# Troopduino.net
KiCad netlist of a schematic drawn in EAGLE
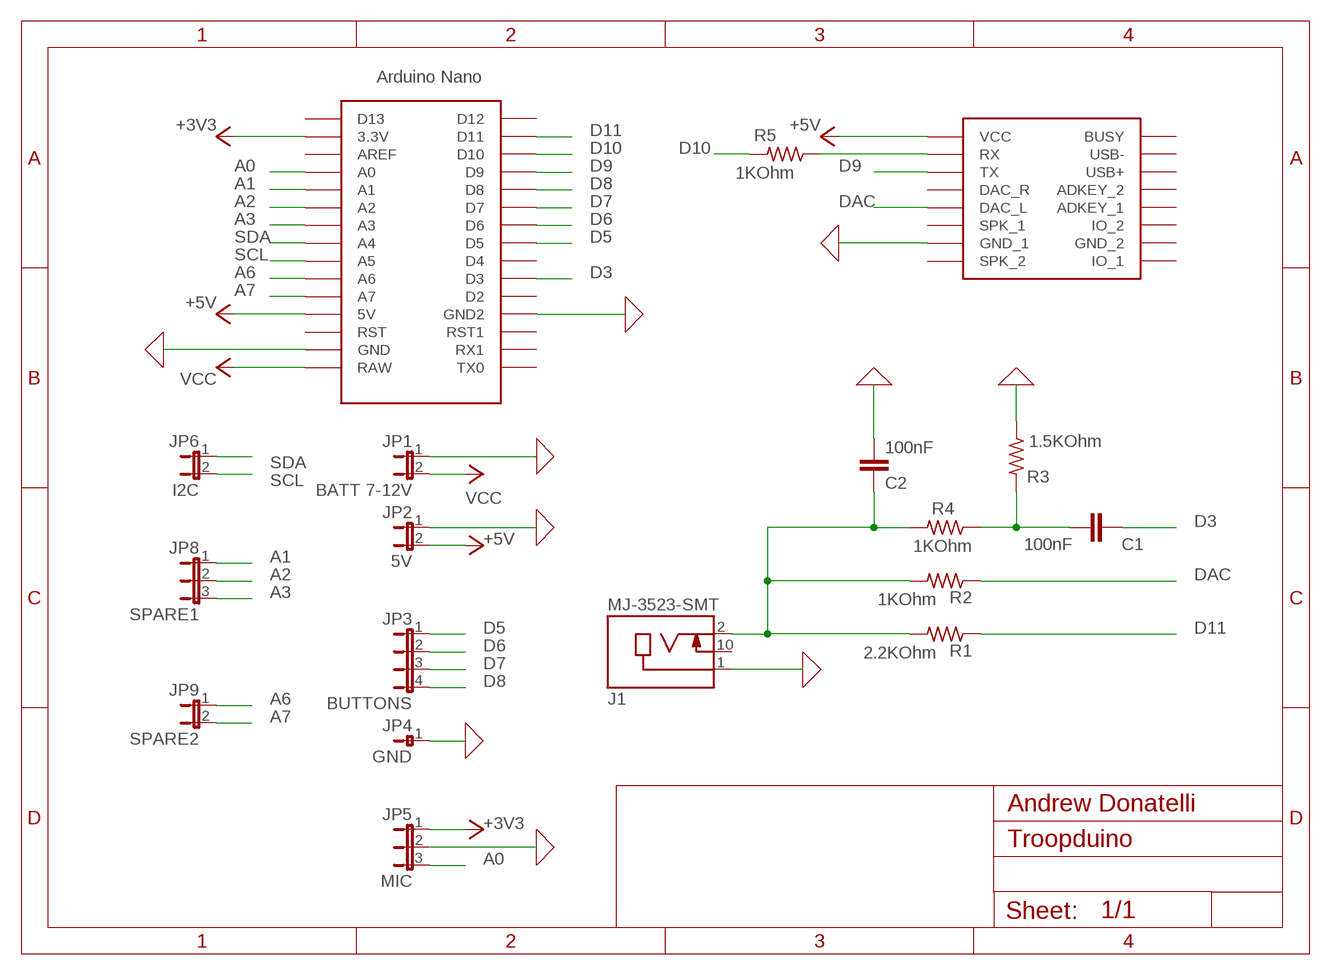
[diagram p0: schematic, sheet 1]

(export (version "E")
  (design (tool "Eeschema 10.0.6"))
  (components
    (comp (ref "C1")
      (value "100nF")
      (footprint "eagle-import:C0805")
      (libsource (lib "eagle-import") (part "C-EUC0805"))
    )
    (comp (ref "C2")
      (value "100nF")
      (footprint "eagle-import:C0805")
      (libsource (lib "eagle-import") (part "C-EUC0805"))
    )
    (comp (ref "J1")
      (value "MJ-3523-SMT")
      (footprint "eagle-import:CUI_MJ-3523-SMT")
      (fields (field (name "MANUFACTURER") "CUI INC"))
      (libsource (lib "eagle-import") (part "MJ-3523-SMT"))
    )
    (comp (ref "JP1")
      (value "BATT 7-12V")
      (footprint "eagle-import:JP1")
      (libsource (lib "eagle-import") (part "JP1E"))
    )
    (comp (ref "JP2")
      (value "5V")
      (footprint "eagle-import:JP1")
      (libsource (lib "eagle-import") (part "JP1E"))
    )
    (comp (ref "JP3")
      (value "BUTTONS")
      (footprint "eagle-import:JP4")
      (libsource (lib "eagle-import") (part "JP4E"))
    )
    (comp (ref "JP4")
      (value "GND")
      (footprint "eagle-import:JP0")
      (libsource (lib "eagle-import") (part "JP0EJP0"))
    )
    (comp (ref "JP5")
      (value "MIC")
      (footprint "eagle-import:JP2")
      (libsource (lib "eagle-import") (part "JP2E"))
    )
    (comp (ref "JP6")
      (value "I2C")
      (footprint "eagle-import:JP1")
      (libsource (lib "eagle-import") (part "JP1E"))
    )
    (comp (ref "JP8")
      (value "SPARE1")
      (footprint "eagle-import:JP2")
      (libsource (lib "eagle-import") (part "JP2E"))
    )
    (comp (ref "JP9")
      (value "SPARE2")
      (footprint "eagle-import:JP1")
      (libsource (lib "eagle-import") (part "JP1E"))
    )
    (comp (ref "R1")
      (value "2.2KOhm")
      (footprint "eagle-import:M0805")
      (libsource (lib "eagle-import") (part "R-US_M0805"))
    )
    (comp (ref "R2")
      (value "1KOhm")
      (footprint "eagle-import:M0805")
      (libsource (lib "eagle-import") (part "R-US_M0805"))
    )
    (comp (ref "R3")
      (value "1.5KOhm")
      (footprint "eagle-import:M0805")
      (libsource (lib "eagle-import") (part "R-US_M0805"))
    )
    (comp (ref "R4")
      (value "1KOhm")
      (footprint "eagle-import:M0805")
      (libsource (lib "eagle-import") (part "R-US_M0805"))
    )
    (comp (ref "R5")
      (value "1KOhm")
      (footprint "eagle-import:M0805")
      (libsource (lib "eagle-import") (part "R-US_M0805"))
    )
    (comp (ref "U$1")
      (value "DFPLAYER")
      (footprint "eagle-import:DFPLAYER")
      (libsource (lib "eagle-import") (part "DFPLAYER"))
    )
    (comp (ref "U$2")
      (value "NANO")
      (footprint "eagle-import:NANO")
      (libsource (lib "eagle-import") (part "NANO"))
    )
  )
  (nets
    (net (code "1") (name "+3V3") (class "Default")
      (node (ref "JP5") (pin "1") (pinfunction "1_1") (pintype "passive"))
      (node (ref "U$2") (pin "3.3V") (pinfunction "3.3V_3.3V") (pintype "bidirectional"))
    )
    (net (code "2") (name "+5V") (class "Default")
      (node (ref "JP2") (pin "2") (pinfunction "2_2") (pintype "passive"))
      (node (ref "U$1") (pin "VCC") (pinfunction "VCC_VCC") (pintype "bidirectional"))
      (node (ref "U$2") (pin "5V") (pinfunction "5V_5V") (pintype "bidirectional"))
    )
    (net (code "3") (name "/A0") (class "Default")
      (node (ref "JP5") (pin "3") (pinfunction "3_3") (pintype "passive"))
      (node (ref "U$2") (pin "A0") (pinfunction "A0_A0") (pintype "bidirectional"))
    )
    (net (code "4") (name "/A1") (class "Default")
      (node (ref "JP8") (pin "1") (pinfunction "1_1") (pintype "passive"))
      (node (ref "U$2") (pin "A1") (pinfunction "A1_A1") (pintype "bidirectional"))
    )
    (net (code "5") (name "/A2") (class "Default")
      (node (ref "JP8") (pin "2") (pinfunction "2_2") (pintype "passive"))
      (node (ref "U$2") (pin "A2") (pinfunction "A2_A2") (pintype "bidirectional"))
    )
    (net (code "6") (name "/A3") (class "Default")
      (node (ref "JP8") (pin "3") (pinfunction "3_3") (pintype "passive"))
      (node (ref "U$2") (pin "A3") (pinfunction "A3_A3") (pintype "bidirectional"))
    )
    (net (code "7") (name "/A6") (class "Default")
      (node (ref "JP9") (pin "1") (pinfunction "1_1") (pintype "passive"))
      (node (ref "U$2") (pin "A6") (pinfunction "A6_A6") (pintype "bidirectional"))
    )
    (net (code "8") (name "/A7") (class "Default")
      (node (ref "JP9") (pin "2") (pinfunction "2_2") (pintype "passive"))
      (node (ref "U$2") (pin "A7") (pinfunction "A7_A7") (pintype "bidirectional"))
    )
    (net (code "9") (name "/D3") (class "Default")
      (node (ref "C1") (pin "1") (pinfunction "1_1") (pintype "passive"))
      (node (ref "U$2") (pin "D3") (pinfunction "D3_D3") (pintype "bidirectional"))
    )
    (net (code "10") (name "/D5") (class "Default")
      (node (ref "JP3") (pin "1") (pinfunction "1_1") (pintype "passive"))
      (node (ref "U$2") (pin "D5") (pinfunction "D5_D5") (pintype "bidirectional"))
    )
    (net (code "11") (name "/D6") (class "Default")
      (node (ref "JP3") (pin "2") (pinfunction "2_2") (pintype "passive"))
      (node (ref "U$2") (pin "D6") (pinfunction "D6_D6") (pintype "bidirectional"))
    )
    (net (code "12") (name "/D7") (class "Default")
      (node (ref "JP3") (pin "3") (pinfunction "3_3") (pintype "passive"))
      (node (ref "U$2") (pin "D7") (pinfunction "D7_D7") (pintype "bidirectional"))
    )
    (net (code "13") (name "/D8") (class "Default")
      (node (ref "JP3") (pin "4") (pinfunction "4_4") (pintype "passive"))
      (node (ref "U$2") (pin "D8") (pinfunction "D8_D8") (pintype "bidirectional"))
    )
    (net (code "14") (name "/D9") (class "Default")
      (node (ref "U$1") (pin "TX") (pinfunction "TX_TX") (pintype "bidirectional"))
      (node (ref "U$2") (pin "D9") (pinfunction "D9_D9") (pintype "bidirectional"))
    )
    (net (code "15") (name "/D10") (class "Default")
      (node (ref "R5") (pin "2") (pinfunction "2_2") (pintype "passive"))
      (node (ref "U$2") (pin "D10") (pinfunction "D10_D10") (pintype "bidirectional"))
    )
    (net (code "16") (name "/D11") (class "Default")
      (node (ref "R1") (pin "1") (pinfunction "1_1") (pintype "passive"))
      (node (ref "U$2") (pin "D11") (pinfunction "D11_D11") (pintype "bidirectional"))
    )
    (net (code "17") (name "/DAC") (class "Default")
      (node (ref "R2") (pin "1") (pinfunction "1_1") (pintype "passive"))
      (node (ref "U$1") (pin "DAC_L") (pinfunction "DAC_L_DAC_L") (pintype "bidirectional"))
    )
    (net (code "18") (name "/SCL") (class "Default")
      (node (ref "JP6") (pin "2") (pinfunction "2_2") (pintype "passive"))
      (node (ref "U$2") (pin "A5") (pinfunction "A5_A5") (pintype "bidirectional"))
    )
    (net (code "19") (name "/SDA") (class "Default")
      (node (ref "JP6") (pin "1") (pinfunction "1_1") (pintype "passive"))
      (node (ref "U$2") (pin "A4") (pinfunction "A4_A4") (pintype "bidirectional"))
    )
    (net (code "20") (name "GND") (class "Default")
      (node (ref "C2") (pin "1") (pinfunction "1_1") (pintype "passive"))
      (node (ref "J1") (pin "1") (pinfunction "1_1") (pintype "passive"))
      (node (ref "JP1") (pin "1") (pinfunction "1_1") (pintype "passive"))
      (node (ref "JP2") (pin "1") (pinfunction "1_1") (pintype "passive"))
      (node (ref "JP4") (pin "1") (pinfunction "1_1") (pintype "passive"))
      (node (ref "JP5") (pin "2") (pinfunction "2_2") (pintype "passive"))
      (node (ref "R3") (pin "1") (pinfunction "1_1") (pintype "passive"))
      (node (ref "U$1") (pin "GND_1") (pinfunction "GND_1_GND_1") (pintype "bidirectional"))
      (node (ref "U$2") (pin "GND") (pinfunction "GND_GND") (pintype "bidirectional"))
      (node (ref "U$2") (pin "GND1") (pinfunction "GND2_GND1") (pintype "bidirectional"))
    )
    (net (code "21") (name "Net-(C1-Pad2)") (class "Default")
      (node (ref "C1") (pin "2") (pinfunction "2_2") (pintype "passive"))
      (node (ref "R3") (pin "2") (pinfunction "2_2") (pintype "passive"))
      (node (ref "R4") (pin "1") (pinfunction "1_1") (pintype "passive"))
    )
    (net (code "22") (name "Net-(C2-Pad2)") (class "Default")
      (node (ref "C2") (pin "2") (pinfunction "2_2") (pintype "passive"))
      (node (ref "J1") (pin "2") (pinfunction "2_2") (pintype "passive"))
      (node (ref "R1") (pin "2") (pinfunction "2_2") (pintype "passive"))
      (node (ref "R2") (pin "2") (pinfunction "2_2") (pintype "passive"))
      (node (ref "R4") (pin "2") (pinfunction "2_2") (pintype "passive"))
    )
    (net (code "23") (name "Net-(R5-Pad1)") (class "Default")
      (node (ref "R5") (pin "1") (pinfunction "1_1") (pintype "passive"))
      (node (ref "U$1") (pin "RX") (pinfunction "RX_RX") (pintype "bidirectional"))
    )
    (net (code "24") (name "VCC") (class "Default")
      (node (ref "JP1") (pin "2") (pinfunction "2_2") (pintype "passive"))
      (node (ref "U$2") (pin "RAW") (pinfunction "RAW_RAW") (pintype "bidirectional"))
    )
    (net (code "25") (name "unconnected-(J1-Pad10)") (class "Default")
      (node (ref "J1") (pin "10") (pinfunction "10_10") (pintype "passive"))
    )
    (net (code "26") (name "unconnected-(U$1-ADKEY_1-PadADKEY1)") (class "Default")
      (node (ref "U$1") (pin "ADKEY1") (pinfunction "ADKEY_1_ADKEY1") (pintype "bidirectional"))
    )
    (net (code "27") (name "unconnected-(U$1-ADKEY_2-PadADKEY2)") (class "Default")
      (node (ref "U$1") (pin "ADKEY2") (pinfunction "ADKEY_2_ADKEY2") (pintype "bidirectional"))
    )
    (net (code "28") (name "unconnected-(U$1-IO_1-PadIO1)") (class "Default")
      (node (ref "U$1") (pin "IO1") (pinfunction "IO_1_IO1") (pintype "bidirectional"))
    )
    (net (code "29") (name "unconnected-(U$1-IO_2-PadIO2)") (class "Default")
      (node (ref "U$1") (pin "IO2") (pinfunction "IO_2_IO2") (pintype "bidirectional"))
    )
    (net (code "30") (name "unconnected-(U$1-PadBUSY)") (class "Default")
      (node (ref "U$1") (pin "BUSY") (pinfunction "BUSY_BUSY") (pintype "bidirectional"))
    )
    (net (code "31") (name "unconnected-(U$1-PadDAC_R)") (class "Default")
      (node (ref "U$1") (pin "DAC_R") (pinfunction "DAC_R_DAC_R") (pintype "bidirectional"))
    )
    (net (code "32") (name "unconnected-(U$1-PadGND_2)") (class "Default")
      (node (ref "U$1") (pin "GND_2") (pinfunction "GND_2_GND_2") (pintype "bidirectional"))
    )
    (net (code "33") (name "unconnected-(U$1-PadUSB+)") (class "Default")
      (node (ref "U$1") (pin "USB+") (pinfunction "USB+_USB+") (pintype "bidirectional"))
    )
    (net (code "34") (name "unconnected-(U$1-PadUSB-)") (class "Default")
      (node (ref "U$1") (pin "USB-") (pinfunction "USB-_USB-") (pintype "bidirectional"))
    )
    (net (code "35") (name "unconnected-(U$1-SPK_1-PadSPK1)") (class "Default")
      (node (ref "U$1") (pin "SPK1") (pinfunction "SPK_1_SPK1") (pintype "bidirectional"))
    )
    (net (code "36") (name "unconnected-(U$1-SPK_2-PadSPK2)") (class "Default")
      (node (ref "U$1") (pin "SPK2") (pinfunction "SPK_2_SPK2") (pintype "bidirectional"))
    )
    (net (code "37") (name "unconnected-(U$2-PadAREF)") (class "Default")
      (node (ref "U$2") (pin "AREF") (pinfunction "AREF_AREF") (pintype "bidirectional"))
    )
    (net (code "38") (name "unconnected-(U$2-PadD2)") (class "Default")
      (node (ref "U$2") (pin "D2") (pinfunction "D2_D2") (pintype "bidirectional"))
    )
    (net (code "39") (name "unconnected-(U$2-PadD4)") (class "Default")
      (node (ref "U$2") (pin "D4") (pinfunction "D4_D4") (pintype "bidirectional"))
    )
    (net (code "40") (name "unconnected-(U$2-PadD12)") (class "Default")
      (node (ref "U$2") (pin "D12") (pinfunction "D12_D12") (pintype "bidirectional"))
    )
    (net (code "41") (name "unconnected-(U$2-PadD13)") (class "Default")
      (node (ref "U$2") (pin "D13") (pinfunction "D13_D13") (pintype "bidirectional"))
    )
    (net (code "42") (name "unconnected-(U$2-PadRST)") (class "Default")
      (node (ref "U$2") (pin "RST") (pinfunction "RST_RST") (pintype "bidirectional"))
    )
    (net (code "43") (name "unconnected-(U$2-PadRST1)") (class "Default")
      (node (ref "U$2") (pin "RST1") (pinfunction "RST1_RST1") (pintype "bidirectional"))
    )
    (net (code "44") (name "unconnected-(U$2-PadRX1)") (class "Default")
      (node (ref "U$2") (pin "RX1") (pinfunction "RX1_RX1") (pintype "bidirectional"))
    )
    (net (code "45") (name "unconnected-(U$2-PadTX0)") (class "Default")
      (node (ref "U$2") (pin "TX0") (pinfunction "TX0_TX0") (pintype "bidirectional"))
    )
  )
)
